# design.net
KiCad netlist of a schematic drawn in EAGLE
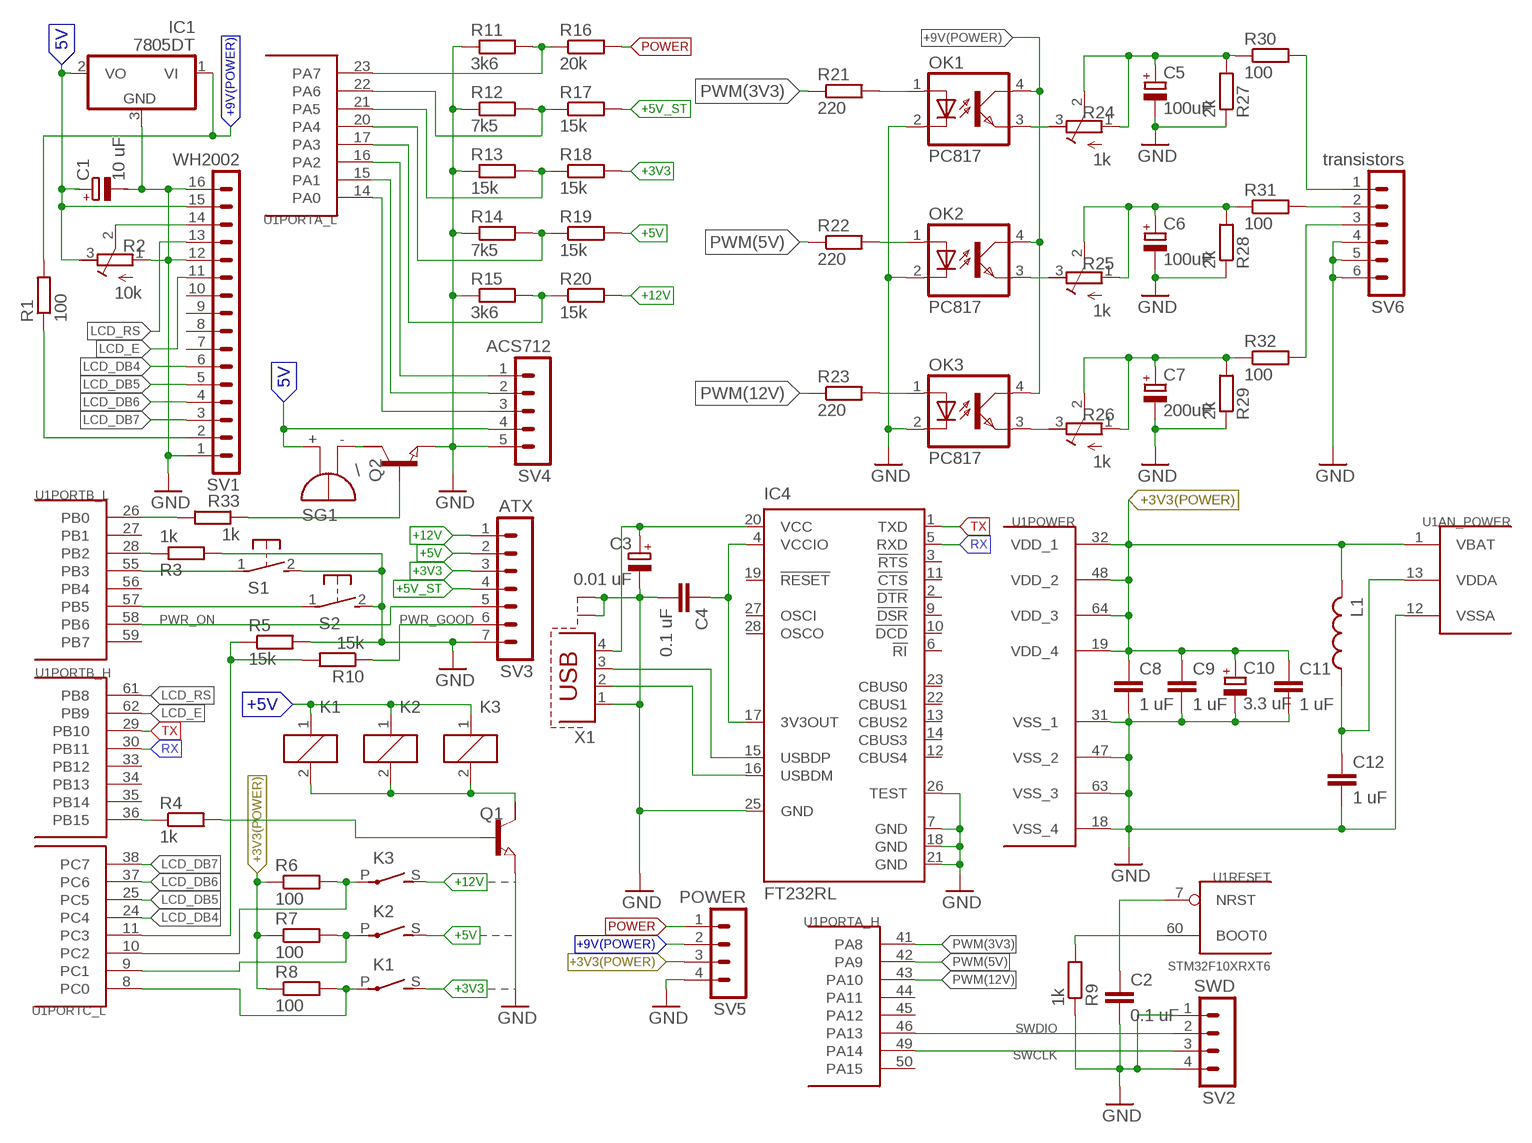
[diagram p0: schematic, sheet 1]

(export (version "E")
  (design (tool "Eeschema 10.0.6"))
  (components
    (comp (ref "C1")
      (value "10 uF")
      (footprint "eagle-import:140CLH-0810")
      (libsource (lib "eagle-import") (part "CPOL-EU140CLH-0810"))
    )
    (comp (ref "C2")
      (value "0.1 uF")
      (footprint "eagle-import:C1206")
      (libsource (lib "eagle-import") (part "C-EUC1206"))
    )
    (comp (ref "C3")
      (value "0.01 uF")
      (footprint "eagle-import:140CLH-0810")
      (libsource (lib "eagle-import") (part "CPOL-EU140CLH-0810"))
    )
    (comp (ref "C4")
      (value "0.1 uF")
      (footprint "eagle-import:C1206")
      (libsource (lib "eagle-import") (part "C-EUC1206"))
    )
    (comp (ref "C5")
      (value "100uF")
      (footprint "eagle-import:140CLH-0810")
      (libsource (lib "eagle-import") (part "CPOL-EU140CLH-0810"))
    )
    (comp (ref "C6")
      (value "100uF")
      (footprint "eagle-import:140CLH-0810")
      (libsource (lib "eagle-import") (part "CPOL-EU140CLH-0810"))
    )
    (comp (ref "C7")
      (value "200uF")
      (footprint "eagle-import:140CLH-0810")
      (libsource (lib "eagle-import") (part "CPOL-EU140CLH-0810"))
    )
    (comp (ref "C8")
      (value "1 uF")
      (footprint "eagle-import:C1206")
      (libsource (lib "eagle-import") (part "C-EUC1206"))
    )
    (comp (ref "C9")
      (value "1 uF")
      (footprint "eagle-import:C1206")
      (libsource (lib "eagle-import") (part "C-EUC1206"))
    )
    (comp (ref "C10")
      (value "3.3 uF")
      (footprint "eagle-import:140CLH-0810")
      (libsource (lib "eagle-import") (part "CPOL-EU140CLH-0810"))
    )
    (comp (ref "C11")
      (value "1 uF")
      (footprint "eagle-import:C1206")
      (libsource (lib "eagle-import") (part "C-EUC1206"))
    )
    (comp (ref "C12")
      (value "1 uF")
      (footprint "eagle-import:C1206")
      (libsource (lib "eagle-import") (part "C-EUC1206"))
    )
    (comp (ref "IC1")
      (value "7805DT")
      (footprint "eagle-import:TO252")
      (libsource (lib "eagle-import") (part "78DT05"))
    )
    (comp (ref "IC4")
      (value "FT232RL")
      (footprint "eagle-import:SSOP28")
      (libsource (lib "eagle-import") (part "FT232RL"))
    )
    (comp (ref "K1")
      (value "G2RA")
      (footprint "eagle-import:G2RA")
      (libsource (lib "eagle-import") (part "G2RA"))
    )
    (comp (ref "K2")
      (value "G2RA")
      (footprint "eagle-import:G2RA")
      (libsource (lib "eagle-import") (part "G2RA"))
    )
    (comp (ref "K3")
      (value "G2RA")
      (footprint "eagle-import:G2RA")
      (libsource (lib "eagle-import") (part "G2RA"))
    )
    (comp (ref "L1")
      (value "L-USL1812")
      (footprint "eagle-import:L1812")
      (libsource (lib "eagle-import") (part "L-USL1812"))
    )
    (comp (ref "OK1")
      (value "PC817")
      (footprint "eagle-import:DIL04")
      (fields (field (name "MPN") "PC817X4J000F"))
      (libsource (lib "eagle-import") (part "PC817"))
    )
    (comp (ref "OK2")
      (value "PC817")
      (footprint "eagle-import:DIL04")
      (fields (field (name "MPN") "PC817X4J000F"))
      (libsource (lib "eagle-import") (part "PC817"))
    )
    (comp (ref "OK3")
      (value "PC817")
      (footprint "eagle-import:DIL04")
      (fields (field (name "MPN") "PC817X4J000F"))
      (libsource (lib "eagle-import") (part "PC817"))
    )
    (comp (ref "Q1")
      (value "NPN-TRANSISTIOR-2COLSOT89")
      (footprint "eagle-import:SOT89")
      (libsource (lib "eagle-import") (part "NPN-TRANSISTIOR-2COLSOT89"))
    )
    (comp (ref "Q2")
      (value "NPN-TRANSISTIOR-2COLSOT89")
      (footprint "eagle-import:SOT89")
      (libsource (lib "eagle-import") (part "NPN-TRANSISTIOR-2COLSOT89"))
    )
    (comp (ref "R1")
      (value "100")
      (footprint "eagle-import:M1206")
      (libsource (lib "eagle-import") (part "R-EU_M1206"))
    )
    (comp (ref "R2")
      (value "10k")
      (footprint "eagle-import:RTRIM4G_J")
      (libsource (lib "eagle-import") (part "R-TRIMM4G/J"))
    )
    (comp (ref "R3")
      (value "1k")
      (footprint "eagle-import:M1206")
      (libsource (lib "eagle-import") (part "R-EU_M1206"))
    )
    (comp (ref "R4")
      (value "1k")
      (footprint "eagle-import:M1206")
      (libsource (lib "eagle-import") (part "R-EU_M1206"))
    )
    (comp (ref "R5")
      (value "15k")
      (footprint "eagle-import:M1206")
      (libsource (lib "eagle-import") (part "R-EU_M1206"))
    )
    (comp (ref "R6")
      (value "100")
      (footprint "eagle-import:M1206")
      (libsource (lib "eagle-import") (part "R-EU_M1206"))
    )
    (comp (ref "R7")
      (value "100")
      (footprint "eagle-import:M1206")
      (libsource (lib "eagle-import") (part "R-EU_M1206"))
    )
    (comp (ref "R8")
      (value "100")
      (footprint "eagle-import:M1206")
      (libsource (lib "eagle-import") (part "R-EU_M1206"))
    )
    (comp (ref "R9")
      (value "1k")
      (footprint "eagle-import:R1206")
      (libsource (lib "eagle-import") (part "R-EU_R1206"))
    )
    (comp (ref "R10")
      (value "15k")
      (footprint "eagle-import:M1206")
      (libsource (lib "eagle-import") (part "R-EU_M1206"))
    )
    (comp (ref "R11")
      (value "3k6")
      (footprint "eagle-import:M1206")
      (libsource (lib "eagle-import") (part "R-EU_M1206"))
    )
    (comp (ref "R12")
      (value "7k5")
      (footprint "eagle-import:M1206")
      (libsource (lib "eagle-import") (part "R-EU_M1206"))
    )
    (comp (ref "R13")
      (value "15k")
      (footprint "eagle-import:M1206")
      (libsource (lib "eagle-import") (part "R-EU_M1206"))
    )
    (comp (ref "R14")
      (value "7k5")
      (footprint "eagle-import:M1206")
      (libsource (lib "eagle-import") (part "R-EU_M1206"))
    )
    (comp (ref "R15")
      (value "3k6")
      (footprint "eagle-import:M1206")
      (libsource (lib "eagle-import") (part "R-EU_M1206"))
    )
    (comp (ref "R16")
      (value "20k")
      (footprint "eagle-import:M1206")
      (libsource (lib "eagle-import") (part "R-EU_M1206"))
    )
    (comp (ref "R17")
      (value "15k")
      (footprint "eagle-import:M1206")
      (libsource (lib "eagle-import") (part "R-EU_M1206"))
    )
    (comp (ref "R18")
      (value "15k")
      (footprint "eagle-import:M1206")
      (libsource (lib "eagle-import") (part "R-EU_M1206"))
    )
    (comp (ref "R19")
      (value "15k")
      (footprint "eagle-import:M1206")
      (libsource (lib "eagle-import") (part "R-EU_M1206"))
    )
    (comp (ref "R20")
      (value "15k")
      (footprint "eagle-import:M1206")
      (libsource (lib "eagle-import") (part "R-EU_M1206"))
    )
    (comp (ref "R21")
      (value "220")
      (footprint "eagle-import:M1206")
      (libsource (lib "eagle-import") (part "R-EU_M1206"))
    )
    (comp (ref "R22")
      (value "220")
      (footprint "eagle-import:M1206")
      (libsource (lib "eagle-import") (part "R-EU_M1206"))
    )
    (comp (ref "R23")
      (value "220")
      (footprint "eagle-import:M1206")
      (libsource (lib "eagle-import") (part "R-EU_M1206"))
    )
    (comp (ref "R24")
      (value "1k")
      (footprint "eagle-import:RTRIM4G_J")
      (libsource (lib "eagle-import") (part "R-TRIMM4G/J"))
    )
    (comp (ref "R25")
      (value "1k")
      (footprint "eagle-import:RTRIM4G_J")
      (libsource (lib "eagle-import") (part "R-TRIMM4G/J"))
    )
    (comp (ref "R26")
      (value "1k")
      (footprint "eagle-import:RTRIM4G_J")
      (libsource (lib "eagle-import") (part "R-TRIMM4G/J"))
    )
    (comp (ref "R27")
      (value "2k")
      (footprint "eagle-import:M1206")
      (libsource (lib "eagle-import") (part "R-EU_M1206"))
    )
    (comp (ref "R28")
      (value "2k")
      (footprint "eagle-import:M1206")
      (libsource (lib "eagle-import") (part "R-EU_M1206"))
    )
    (comp (ref "R29")
      (value "2k")
      (footprint "eagle-import:M1206")
      (libsource (lib "eagle-import") (part "R-EU_M1206"))
    )
    (comp (ref "R30")
      (value "100")
      (footprint "eagle-import:M1206")
      (libsource (lib "eagle-import") (part "R-EU_M1206"))
    )
    (comp (ref "R31")
      (value "100")
      (footprint "eagle-import:M1206")
      (libsource (lib "eagle-import") (part "R-EU_M1206"))
    )
    (comp (ref "R32")
      (value "100")
      (footprint "eagle-import:M1206")
      (libsource (lib "eagle-import") (part "R-EU_M1206"))
    )
    (comp (ref "R33")
      (value "1k")
      (footprint "eagle-import:M1206")
      (libsource (lib "eagle-import") (part "R-EU_M1206"))
    )
    (comp (ref "S1")
      (value "31-XX")
      (footprint "eagle-import:B3F-31XX")
      (fields (field (name "MPN") "B3F-3100"))
      (libsource (lib "eagle-import") (part "31-XX"))
    )
    (comp (ref "S2")
      (value "31-XX")
      (footprint "eagle-import:B3F-31XX")
      (fields (field (name "MPN") "B3F-3100"))
      (libsource (lib "eagle-import") (part "31-XX"))
    )
    (comp (ref "SG1")
      (value "\\")
      (footprint "eagle-import:F_BC35")
      (libsource (lib "eagle-import") (part "F/BC35"))
    )
    (comp (ref "SV1")
      (value "WH2002")
      (footprint "eagle-import:MICS-16")
      (libsource (lib "eagle-import") (part "MICS-16"))
    )
    (comp (ref "SV2")
      (value "SWD")
      (footprint "eagle-import:MA04-1")
      (libsource (lib "eagle-import") (part "MA04-1"))
    )
    (comp (ref "SV3")
      (value "ATX")
      (footprint "eagle-import:MA07-1")
      (libsource (lib "eagle-import") (part "MA07-1"))
    )
    (comp (ref "SV4")
      (value "ACS712")
      (footprint "eagle-import:MA05-1")
      (libsource (lib "eagle-import") (part "MA05-1"))
    )
    (comp (ref "SV5")
      (value "POWER")
      (footprint "eagle-import:MA04-1")
      (libsource (lib "eagle-import") (part "MA04-1"))
    )
    (comp (ref "SV6")
      (value "transistors")
      (footprint "eagle-import:MA06-1")
      (libsource (lib "eagle-import") (part "MA06-1"))
    )
    (comp (ref "U1")
      (value "STM32F10XRXT6")
      (footprint "eagle-import:TQFP64")
      (libsource (lib "eagle-import") (part "STM32F10XRXT6"))
    )
    (comp (ref "X1")
      (value "PN61729-S")
      (footprint "eagle-import:PN61729-S")
      (libsource (lib "eagle-import") (part "PN61729-S"))
    )
  )
  (nets
    (net (code "1") (name "+3V3") (class "Default")
      (node (ref "K1") (pin "S") (pinfunction "S_S") (pintype "passive"))
      (node (ref "R18") (pin "2") (pinfunction "2_2") (pintype "passive"))
      (node (ref "SV3") (pin "3") (pinfunction "3_3") (pintype "passive"))
    )
    (net (code "2") (name "+3V3(POWER)") (class "Default")
      (node (ref "C10") (pin "+") (pinfunction "+_+") (pintype "passive"))
      (node (ref "C11") (pin "1") (pinfunction "1_1") (pintype "passive"))
      (node (ref "C8") (pin "1") (pinfunction "1_1") (pintype "passive"))
      (node (ref "C9") (pin "1") (pinfunction "1_1") (pintype "passive"))
      (node (ref "L1") (pin "2") (pinfunction "2_2") (pintype "passive"))
      (node (ref "SV5") (pin "3") (pinfunction "3_3") (pintype "passive"))
      (node (ref "U1") (pin "1") (pinfunction "VBAT_1") (pintype "power_in"))
      (node (ref "U1") (pin "19") (pinfunction "VDD_4_19") (pintype "power_in"))
      (node (ref "U1") (pin "32") (pinfunction "VDD_1_32") (pintype "power_in"))
      (node (ref "U1") (pin "48") (pinfunction "VDD_2_48") (pintype "power_in"))
      (node (ref "U1") (pin "64") (pinfunction "VDD_3_64") (pintype "power_in"))
    )
    (net (code "3") (name "+5V") (class "Default")
      (node (ref "K1") (pin "1") (pinfunction "1_1") (pintype "passive"))
      (node (ref "K2") (pin "1") (pinfunction "1_1") (pintype "passive"))
      (node (ref "K2") (pin "S") (pinfunction "S_S") (pintype "passive"))
      (node (ref "K3") (pin "1") (pinfunction "1_1") (pintype "passive"))
      (node (ref "R19") (pin "2") (pinfunction "2_2") (pintype "passive"))
      (node (ref "SV3") (pin "2") (pinfunction "2_2") (pintype "passive"))
    )
    (net (code "4") (name "+5V_ST") (class "Default")
      (node (ref "R17") (pin "2") (pinfunction "2_2") (pintype "passive"))
      (node (ref "SV3") (pin "4") (pinfunction "4_4") (pintype "passive"))
    )
    (net (code "5") (name "+9V(POWER)") (class "Default")
      (node (ref "IC1") (pin "1") (pinfunction "VI_1") (pintype "input"))
      (node (ref "OK1") (pin "4") (pinfunction "COL_4") (pintype "passive"))
      (node (ref "OK2") (pin "4") (pinfunction "COL_4") (pintype "passive"))
      (node (ref "OK3") (pin "4") (pinfunction "COL_4") (pintype "passive"))
      (node (ref "R1") (pin "2") (pinfunction "2_2") (pintype "passive"))
      (node (ref "SV5") (pin "2") (pinfunction "2_2") (pintype "passive"))
    )
    (net (code "6") (name "+12V") (class "Default")
      (node (ref "K3") (pin "S") (pinfunction "S_S") (pintype "passive"))
      (node (ref "R20") (pin "2") (pinfunction "2_2") (pintype "passive"))
      (node (ref "SV3") (pin "1") (pinfunction "1_1") (pintype "passive"))
    )
    (net (code "7") (name "/PWR_GOOD") (class "Default")
      (node (ref "R10") (pin "1") (pinfunction "1_1") (pintype "passive"))
      (node (ref "SV3") (pin "6") (pinfunction "6_6") (pintype "passive"))
    )
    (net (code "8") (name "/PWR_ON") (class "Default")
      (node (ref "SV3") (pin "5") (pinfunction "5_5") (pintype "passive"))
      (node (ref "U1") (pin "58") (pinfunction "PB6_58") (pintype "bidirectional"))
    )
    (net (code "9") (name "/SWCLK") (class "Default")
      (node (ref "SV2") (pin "3") (pinfunction "3_3") (pintype "passive"))
      (node (ref "U1") (pin "49") (pinfunction "PA14_49") (pintype "bidirectional"))
    )
    (net (code "10") (name "/SWDIO") (class "Default")
      (node (ref "SV2") (pin "2") (pinfunction "2_2") (pintype "passive"))
      (node (ref "U1") (pin "46") (pinfunction "PA13_46") (pintype "bidirectional"))
    )
    (net (code "11") (name "5V") (class "Default")
      (node (ref "C1") (pin "+") (pinfunction "+_+") (pintype "passive"))
      (node (ref "IC1") (pin "2") (pinfunction "VO_2") (pintype "passive"))
      (node (ref "R2") (pin "3") (pinfunction "A_3") (pintype "passive"))
      (node (ref "SG1") (pin "+") (pinfunction "+_+") (pintype "passive"))
      (node (ref "SV1") (pin "15") (pinfunction "15_15") (pintype "passive"))
      (node (ref "SV4") (pin "4") (pinfunction "4_4") (pintype "passive"))
    )
    (net (code "12") (name "GND") (class "Default")
      (node (ref "C1") (pin "-") (pinfunction "-_-") (pintype "passive"))
      (node (ref "C10") (pin "-") (pinfunction "-_-") (pintype "passive"))
      (node (ref "C11") (pin "2") (pinfunction "2_2") (pintype "passive"))
      (node (ref "C12") (pin "2") (pinfunction "2_2") (pintype "passive"))
      (node (ref "C2") (pin "2") (pinfunction "2_2") (pintype "passive"))
      (node (ref "C3") (pin "-") (pinfunction "-_-") (pintype "passive"))
      (node (ref "C4") (pin "2") (pinfunction "2_2") (pintype "passive"))
      (node (ref "C5") (pin "-") (pinfunction "-_-") (pintype "passive"))
      (node (ref "C6") (pin "-") (pinfunction "-_-") (pintype "passive"))
      (node (ref "C7") (pin "-") (pinfunction "-_-") (pintype "passive"))
      (node (ref "C8") (pin "2") (pinfunction "2_2") (pintype "passive"))
      (node (ref "C9") (pin "2") (pinfunction "2_2") (pintype "passive"))
      (node (ref "IC1") (pin "3") (pinfunction "GND_3") (pintype "passive"))
      (node (ref "IC4") (pin "18") (pinfunction "GND_18") (pintype "power_in"))
      (node (ref "IC4") (pin "21") (pinfunction "GND_21") (pintype "power_in"))
      (node (ref "IC4") (pin "25") (pinfunction "GND_25") (pintype "power_in"))
      (node (ref "IC4") (pin "26") (pinfunction "TEST_26") (pintype "input"))
      (node (ref "IC4") (pin "7") (pinfunction "GND_7") (pintype "power_in"))
      (node (ref "OK1") (pin "2") (pinfunction "C_2") (pintype "passive"))
      (node (ref "OK2") (pin "2") (pinfunction "C_2") (pintype "passive"))
      (node (ref "OK3") (pin "2") (pinfunction "C_2") (pintype "passive"))
      (node (ref "Q1") (pin "3") (pinfunction "E_3") (pintype "passive"))
      (node (ref "Q2") (pin "3") (pinfunction "E_3") (pintype "passive"))
      (node (ref "R11") (pin "1") (pinfunction "1_1") (pintype "passive"))
      (node (ref "R12") (pin "1") (pinfunction "1_1") (pintype "passive"))
      (node (ref "R13") (pin "1") (pinfunction "1_1") (pintype "passive"))
      (node (ref "R14") (pin "1") (pinfunction "1_1") (pintype "passive"))
      (node (ref "R15") (pin "1") (pinfunction "1_1") (pintype "passive"))
      (node (ref "R2") (pin "1") (pinfunction "E_1") (pintype "passive"))
      (node (ref "R27") (pin "1") (pinfunction "1_1") (pintype "passive"))
      (node (ref "R28") (pin "1") (pinfunction "1_1") (pintype "passive"))
      (node (ref "R29") (pin "1") (pinfunction "1_1") (pintype "passive"))
      (node (ref "R3") (pin "2") (pinfunction "2_2") (pintype "passive"))
      (node (ref "R5") (pin "2") (pinfunction "2_2") (pintype "passive"))
      (node (ref "R9") (pin "1") (pinfunction "1_1") (pintype "passive"))
      (node (ref "S1") (pin "2") (pinfunction "S_2") (pintype "passive"))
      (node (ref "S2") (pin "2") (pinfunction "S_2") (pintype "passive"))
      (node (ref "SV1") (pin "1") (pinfunction "1_1") (pintype "passive"))
      (node (ref "SV1") (pin "12") (pinfunction "12_12") (pintype "passive"))
      (node (ref "SV1") (pin "16") (pinfunction "16_16") (pintype "passive"))
      (node (ref "SV2") (pin "1") (pinfunction "1_1") (pintype "passive"))
      (node (ref "SV2") (pin "4") (pinfunction "4_4") (pintype "passive"))
      (node (ref "SV3") (pin "7") (pinfunction "7_7") (pintype "passive"))
      (node (ref "SV4") (pin "5") (pinfunction "5_5") (pintype "passive"))
      (node (ref "SV5") (pin "4") (pinfunction "4_4") (pintype "passive"))
      (node (ref "SV6") (pin "4") (pinfunction "4_4") (pintype "passive"))
      (node (ref "SV6") (pin "5") (pinfunction "5_5") (pintype "passive"))
      (node (ref "SV6") (pin "6") (pinfunction "6_6") (pintype "passive"))
      (node (ref "U1") (pin "12") (pinfunction "VSSA_12") (pintype "power_in"))
      (node (ref "U1") (pin "18") (pinfunction "VSS_4_18") (pintype "power_in"))
      (node (ref "U1") (pin "31") (pinfunction "VSS_1_31") (pintype "power_in"))
      (node (ref "U1") (pin "47") (pinfunction "VSS_2_47") (pintype "power_in"))
      (node (ref "U1") (pin "63") (pinfunction "VSS_3_63") (pintype "power_in"))
      (node (ref "X1") (pin "1") (pinfunction "1_1") (pintype "passive"))
      (node (ref "X1") (pin "S1") (pinfunction "S1_S1") (pintype "passive"))
      (node (ref "X1") (pin "S2") (pinfunction "S2_S2") (pintype "passive"))
    )
    (net (code "13") (name "LCD_DB4") (class "Default")
      (node (ref "SV1") (pin "6") (pinfunction "6_6") (pintype "passive"))
      (node (ref "U1") (pin "24") (pinfunction "PC4_24") (pintype "bidirectional"))
    )
    (net (code "14") (name "LCD_DB5") (class "Default")
      (node (ref "SV1") (pin "5") (pinfunction "5_5") (pintype "passive"))
      (node (ref "U1") (pin "25") (pinfunction "PC5_25") (pintype "bidirectional"))
    )
    (net (code "15") (name "LCD_DB6") (class "Default")
      (node (ref "SV1") (pin "4") (pinfunction "4_4") (pintype "passive"))
      (node (ref "U1") (pin "37") (pinfunction "PC6_37") (pintype "bidirectional"))
    )
    (net (code "16") (name "LCD_DB7") (class "Default")
      (node (ref "SV1") (pin "3") (pinfunction "3_3") (pintype "passive"))
      (node (ref "U1") (pin "38") (pinfunction "PC7_38") (pintype "bidirectional"))
    )
    (net (code "17") (name "LCD_E") (class "Default")
      (node (ref "SV1") (pin "11") (pinfunction "11_11") (pintype "passive"))
      (node (ref "U1") (pin "62") (pinfunction "PB9_62") (pintype "bidirectional"))
    )
    (net (code "18") (name "LCD_RS") (class "Default")
      (node (ref "SV1") (pin "13") (pinfunction "13_13") (pintype "passive"))
      (node (ref "U1") (pin "61") (pinfunction "PB8_61") (pintype "bidirectional"))
    )
    (net (code "19") (name "Net-(IC4-3V3OUT)") (class "Default")
      (node (ref "C4") (pin "1") (pinfunction "1_1") (pintype "passive"))
      (node (ref "IC4") (pin "17") (pinfunction "3V3OUT_17") (pintype "output"))
      (node (ref "IC4") (pin "4") (pinfunction "VCCIO_4") (pintype "power_in"))
    )
    (net (code "20") (name "Net-(IC4-USBDM)") (class "Default")
      (node (ref "IC4") (pin "16") (pinfunction "USBDM_16") (pintype "bidirectional"))
      (node (ref "X1") (pin "2") (pinfunction "2_2") (pintype "passive"))
    )
    (net (code "21") (name "Net-(IC4-USBDP)") (class "Default")
      (node (ref "IC4") (pin "15") (pinfunction "USBDP_15") (pintype "bidirectional"))
      (node (ref "X1") (pin "3") (pinfunction "3_3") (pintype "passive"))
    )
    (net (code "22") (name "Net-(IC4-VCC)") (class "Default")
      (node (ref "C3") (pin "+") (pinfunction "+_+") (pintype "passive"))
      (node (ref "IC4") (pin "20") (pinfunction "VCC_20") (pintype "power_in"))
      (node (ref "X1") (pin "4") (pinfunction "4_4") (pintype "passive"))
    )
    (net (code "23") (name "Net-(OK1-A)") (class "Default")
      (node (ref "OK1") (pin "1") (pinfunction "A_1") (pintype "passive"))
      (node (ref "R21") (pin "2") (pinfunction "2_2") (pintype "passive"))
    )
    (net (code "24") (name "Net-(OK1-EMIT)") (class "Default")
      (node (ref "OK1") (pin "3") (pinfunction "EMIT_3") (pintype "passive"))
      (node (ref "R24") (pin "3") (pinfunction "A_3") (pintype "passive"))
    )
    (net (code "25") (name "Net-(OK2-A)") (class "Default")
      (node (ref "OK2") (pin "1") (pinfunction "A_1") (pintype "passive"))
      (node (ref "R22") (pin "2") (pinfunction "2_2") (pintype "passive"))
    )
    (net (code "26") (name "Net-(OK2-EMIT)") (class "Default")
      (node (ref "OK2") (pin "3") (pinfunction "EMIT_3") (pintype "passive"))
      (node (ref "R25") (pin "3") (pinfunction "A_3") (pintype "passive"))
    )
    (net (code "27") (name "Net-(OK3-A)") (class "Default")
      (node (ref "OK3") (pin "1") (pinfunction "A_1") (pintype "passive"))
      (node (ref "R23") (pin "2") (pinfunction "2_2") (pintype "passive"))
    )
    (net (code "28") (name "Net-(OK3-EMIT)") (class "Default")
      (node (ref "OK3") (pin "3") (pinfunction "EMIT_3") (pintype "passive"))
      (node (ref "R26") (pin "3") (pinfunction "A_3") (pintype "passive"))
    )
    (net (code "29") (name "Net-(Q1-B)") (class "Default")
      (node (ref "Q1") (pin "1") (pinfunction "B_1") (pintype "passive"))
      (node (ref "R4") (pin "2") (pinfunction "2_2") (pintype "passive"))
    )
    (net (code "30") (name "Net-(Q1-C)") (class "Default")
      (node (ref "K1") (pin "2") (pinfunction "2_2") (pintype "passive"))
      (node (ref "K2") (pin "2") (pinfunction "2_2") (pintype "passive"))
      (node (ref "K3") (pin "2") (pinfunction "2_2") (pintype "passive"))
      (node (ref "Q1") (pin "2") (pinfunction "C_2") (pintype "passive"))
    )
    (net (code "31") (name "Net-(Q2-B)") (class "Default")
      (node (ref "Q2") (pin "1") (pinfunction "B_1") (pintype "passive"))
      (node (ref "R33") (pin "1") (pinfunction "1_1") (pintype "passive"))
    )
    (net (code "32") (name "Net-(Q2-C)") (class "Default")
      (node (ref "Q2") (pin "2") (pinfunction "C_2") (pintype "passive"))
      (node (ref "SG1") (pin "-") (pinfunction "-_-") (pintype "passive"))
    )
    (net (code "33") (name "Net-(R1-Pad1)") (class "Default")
      (node (ref "R1") (pin "1") (pinfunction "1_1") (pintype "passive"))
      (node (ref "SV1") (pin "2") (pinfunction "2_2") (pintype "passive"))
    )
    (net (code "34") (name "Net-(R2-S)") (class "Default")
      (node (ref "R2") (pin "2") (pinfunction "S_2") (pintype "passive"))
      (node (ref "SV1") (pin "14") (pinfunction "14_14") (pintype "passive"))
    )
    (net (code "35") (name "Net-(R6-Pad1)") (class "Default")
      (node (ref "R6") (pin "1") (pinfunction "1_1") (pintype "passive"))
      (node (ref "R7") (pin "1") (pinfunction "1_1") (pintype "passive"))
      (node (ref "R8") (pin "1") (pinfunction "1_1") (pintype "passive"))
    )
    (net (code "36") (name "Net-(R24-E)") (class "Default")
      (node (ref "C5") (pin "+") (pinfunction "+_+") (pintype "passive"))
      (node (ref "R24") (pin "1") (pinfunction "E_1") (pintype "passive"))
      (node (ref "R24") (pin "2") (pinfunction "S_2") (pintype "passive"))
      (node (ref "R27") (pin "2") (pinfunction "2_2") (pintype "passive"))
      (node (ref "R30") (pin "1") (pinfunction "1_1") (pintype "passive"))
    )
    (net (code "37") (name "Net-(R25-E)") (class "Default")
      (node (ref "C6") (pin "+") (pinfunction "+_+") (pintype "passive"))
      (node (ref "R25") (pin "1") (pinfunction "E_1") (pintype "passive"))
      (node (ref "R25") (pin "2") (pinfunction "S_2") (pintype "passive"))
      (node (ref "R28") (pin "2") (pinfunction "2_2") (pintype "passive"))
      (node (ref "R31") (pin "1") (pinfunction "1_1") (pintype "passive"))
    )
    (net (code "38") (name "Net-(R26-E)") (class "Default")
      (node (ref "C7") (pin "+") (pinfunction "+_+") (pintype "passive"))
      (node (ref "R26") (pin "1") (pinfunction "E_1") (pintype "passive"))
      (node (ref "R26") (pin "2") (pinfunction "S_2") (pintype "passive"))
      (node (ref "R29") (pin "2") (pinfunction "2_2") (pintype "passive"))
      (node (ref "R32") (pin "1") (pinfunction "1_1") (pintype "passive"))
    )
    (net (code "39") (name "Net-(R30-Pad2)") (class "Default")
      (node (ref "R30") (pin "2") (pinfunction "2_2") (pintype "passive"))
      (node (ref "SV6") (pin "1") (pinfunction "1_1") (pintype "passive"))
    )
    (net (code "40") (name "Net-(R31-Pad2)") (class "Default")
      (node (ref "R31") (pin "2") (pinfunction "2_2") (pintype "passive"))
      (node (ref "SV6") (pin "2") (pinfunction "2_2") (pintype "passive"))
    )
    (net (code "41") (name "Net-(R32-Pad2)") (class "Default")
      (node (ref "R32") (pin "2") (pinfunction "2_2") (pintype "passive"))
      (node (ref "SV6") (pin "3") (pinfunction "3_3") (pintype "passive"))
    )
    (net (code "42") (name "Net-(S1-P)") (class "Default")
      (node (ref "S1") (pin "1") (pinfunction "P_1") (pintype "passive"))
      (node (ref "U1") (pin "55") (pinfunction "PB3_55") (pintype "bidirectional"))
    )
    (net (code "43") (name "Net-(S2-P)") (class "Default")
      (node (ref "S2") (pin "1") (pinfunction "P_1") (pintype "passive"))
      (node (ref "U1") (pin "57") (pinfunction "PB5_57") (pintype "bidirectional"))
    )
    (net (code "44") (name "Net-(U1A-VDDA)") (class "Default")
      (node (ref "C12") (pin "1") (pinfunction "1_1") (pintype "passive"))
      (node (ref "L1") (pin "1") (pinfunction "1_1") (pintype "passive"))
      (node (ref "U1") (pin "13") (pinfunction "VDDA_13") (pintype "power_in"))
    )
    (net (code "45") (name "Net-(U1C-PA0)") (class "Default")
      (node (ref "SV4") (pin "3") (pinfunction "3_3") (pintype "passive"))
      (node (ref "U1") (pin "14") (pinfunction "PA0_14") (pintype "bidirectional"))
    )
    (net (code "46") (name "Net-(U1C-PA1)") (class "Default")
      (node (ref "SV4") (pin "2") (pinfunction "2_2") (pintype "passive"))
      (node (ref "U1") (pin "15") (pinfunction "PA1_15") (pintype "bidirectional"))
    )
    (net (code "47") (name "Net-(U1C-PA2)") (class "Default")
      (node (ref "SV4") (pin "1") (pinfunction "1_1") (pintype "passive"))
      (node (ref "U1") (pin "16") (pinfunction "PA2_16") (pintype "bidirectional"))
    )
    (net (code "48") (name "Net-(U1C-PA3)") (class "Default")
      (node (ref "R15") (pin "2") (pinfunction "2_2") (pintype "passive"))
      (node (ref "R20") (pin "1") (pinfunction "1_1") (pintype "passive"))
      (node (ref "U1") (pin "17") (pinfunction "PA3_17") (pintype "bidirectional"))
    )
    (net (code "49") (name "Net-(U1C-PA4)") (class "Default")
      (node (ref "R14") (pin "2") (pinfunction "2_2") (pintype "passive"))
      (node (ref "R19") (pin "1") (pinfunction "1_1") (pintype "passive"))
      (node (ref "U1") (pin "20") (pinfunction "PA4_20") (pintype "bidirectional"))
    )
    (net (code "50") (name "Net-(U1C-PA5)") (class "Default")
      (node (ref "R13") (pin "2") (pinfunction "2_2") (pintype "passive"))
      (node (ref "R18") (pin "1") (pinfunction "1_1") (pintype "passive"))
      (node (ref "U1") (pin "21") (pinfunction "PA5_21") (pintype "bidirectional"))
    )
    (net (code "51") (name "Net-(U1C-PA6)") (class "Default")
      (node (ref "R12") (pin "2") (pinfunction "2_2") (pintype "passive"))
      (node (ref "R17") (pin "1") (pinfunction "1_1") (pintype "passive"))
      (node (ref "U1") (pin "22") (pinfunction "PA6_22") (pintype "bidirectional"))
    )
    (net (code "52") (name "Net-(U1C-PA7)") (class "Default")
      (node (ref "R11") (pin "2") (pinfunction "2_2") (pintype "passive"))
      (node (ref "R16") (pin "1") (pinfunction "1_1") (pintype "passive"))
      (node (ref "U1") (pin "23") (pinfunction "PA7_23") (pintype "bidirectional"))
    )
    (net (code "53") (name "Net-(U1D-PB15)") (class "Default")
      (node (ref "R4") (pin "1") (pinfunction "1_1") (pintype "passive"))
      (node (ref "U1") (pin "36") (pinfunction "PB15_36") (pintype "bidirectional"))
    )
    (net (code "54") (name "Net-(U1E-PB0)") (class "Default")
      (node (ref "R33") (pin "2") (pinfunction "2_2") (pintype "passive"))
      (node (ref "U1") (pin "26") (pinfunction "PB0_26") (pintype "bidirectional"))
    )
    (net (code "55") (name "Net-(U1E-PB2)") (class "Default")
      (node (ref "R3") (pin "1") (pinfunction "1_1") (pintype "passive"))
      (node (ref "U1") (pin "28") (pinfunction "PB2_28") (pintype "bidirectional"))
    )
    (net (code "56") (name "Net-(U1G-PC0)") (class "Default")
      (node (ref "K1") (pin "P") (pinfunction "P_P") (pintype "passive"))
      (node (ref "R8") (pin "2") (pinfunction "2_2") (pintype "passive"))
      (node (ref "U1") (pin "8") (pinfunction "PC0_8") (pintype "bidirectional"))
    )
    (net (code "57") (name "Net-(U1G-PC1)") (class "Default")
      (node (ref "K2") (pin "P") (pinfunction "P_P") (pintype "passive"))
      (node (ref "R7") (pin "2") (pinfunction "2_2") (pintype "passive"))
      (node (ref "U1") (pin "9") (pinfunction "PC1_9") (pintype "bidirectional"))
    )
    (net (code "58") (name "Net-(U1G-PC2)") (class "Default")
      (node (ref "K3") (pin "P") (pinfunction "P_P") (pintype "passive"))
      (node (ref "R6") (pin "2") (pinfunction "2_2") (pintype "passive"))
      (node (ref "U1") (pin "10") (pinfunction "PC2_10") (pintype "bidirectional"))
    )
    (net (code "59") (name "Net-(U1G-PC3)") (class "Default")
      (node (ref "R10") (pin "2") (pinfunction "2_2") (pintype "passive"))
      (node (ref "R5") (pin "1") (pinfunction "1_1") (pintype "passive"))
      (node (ref "U1") (pin "11") (pinfunction "PC3_11") (pintype "bidirectional"))
    )
    (net (code "60") (name "Net-(U1J-BOOT0)") (class "Default")
      (node (ref "R9") (pin "2") (pinfunction "2_2") (pintype "passive"))
      (node (ref "U1") (pin "60") (pinfunction "BOOT0_60") (pintype "input"))
    )
    (net (code "61") (name "Net-(U1J-NRST)") (class "Default")
      (node (ref "C2") (pin "1") (pinfunction "1_1") (pintype "passive"))
      (node (ref "U1") (pin "7") (pinfunction "NRST_7") (pintype "input"))
    )
    (net (code "62") (name "POWER") (class "Default")
      (node (ref "R16") (pin "2") (pinfunction "2_2") (pintype "passive"))
      (node (ref "SV5") (pin "1") (pinfunction "1_1") (pintype "passive"))
    )
    (net (code "63") (name "PWM(3V3)") (class "Default")
      (node (ref "R21") (pin "1") (pinfunction "1_1") (pintype "passive"))
      (node (ref "U1") (pin "41") (pinfunction "PA8_41") (pintype "bidirectional"))
    )
    (net (code "64") (name "PWM(5V)") (class "Default")
      (node (ref "R22") (pin "1") (pinfunction "1_1") (pintype "passive"))
      (node (ref "U1") (pin "42") (pinfunction "PA9_42") (pintype "bidirectional"))
    )
    (net (code "65") (name "PWM(12V)") (class "Default")
      (node (ref "R23") (pin "1") (pinfunction "1_1") (pintype "passive"))
      (node (ref "U1") (pin "43") (pinfunction "PA10_43") (pintype "bidirectional"))
    )
    (net (code "66") (name "RX") (class "Default")
      (node (ref "IC4") (pin "5") (pinfunction "RXD_5") (pintype "input"))
      (node (ref "U1") (pin "30") (pinfunction "PB11_30") (pintype "bidirectional"))
    )
    (net (code "67") (name "TX") (class "Default")
      (node (ref "IC4") (pin "1") (pinfunction "TXD_1") (pintype "output"))
      (node (ref "U1") (pin "29") (pinfunction "PB10_29") (pintype "bidirectional"))
    )
    (net (code "68") (name "unconnected-(IC4-CBUS0-Pad23)") (class "Default")
      (node (ref "IC4") (pin "23") (pinfunction "CBUS0_23") (pintype "bidirectional"))
    )
    (net (code "69") (name "unconnected-(IC4-CBUS1-Pad22)") (class "Default")
      (node (ref "IC4") (pin "22") (pinfunction "CBUS1_22") (pintype "bidirectional"))
    )
    (net (code "70") (name "unconnected-(IC4-CBUS2-Pad13)") (class "Default")
      (node (ref "IC4") (pin "13") (pinfunction "CBUS2_13") (pintype "bidirectional"))
    )
    (net (code "71") (name "unconnected-(IC4-CBUS3-Pad14)") (class "Default")
      (node (ref "IC4") (pin "14") (pinfunction "CBUS3_14") (pintype "bidirectional"))
    )
    (net (code "72") (name "unconnected-(IC4-CBUS4-Pad12)") (class "Default")
      (node (ref "IC4") (pin "12") (pinfunction "CBUS4_12") (pintype "bidirectional"))
    )
    (net (code "73") (name "unconnected-(IC4-OSCI-Pad27)") (class "Default")
      (node (ref "IC4") (pin "27") (pinfunction "OSCI_27") (pintype "input"))
    )
    (net (code "74") (name "unconnected-(IC4-OSCO-Pad28)") (class "Default")
      (node (ref "IC4") (pin "28") (pinfunction "OSCO_28") (pintype "output"))
    )
    (net (code "75") (name "unconnected-(IC4-~{CTS}-Pad11)") (class "Default")
      (node (ref "IC4") (pin "11") (pinfunction "~{CTS}_11") (pintype "input"))
    )
    (net (code "76") (name "unconnected-(IC4-~{DCD}-Pad10)") (class "Default")
      (node (ref "IC4") (pin "10") (pinfunction "~{DCD}_10") (pintype "input"))
    )
    (net (code "77") (name "unconnected-(IC4-~{DSR}-Pad9)") (class "Default")
      (node (ref "IC4") (pin "9") (pinfunction "~{DSR}_9") (pintype "input"))
    )
    (net (code "78") (name "unconnected-(IC4-~{DTR}-Pad2)") (class "Default")
      (node (ref "IC4") (pin "2") (pinfunction "~{DTR}_2") (pintype "output"))
    )
    (net (code "79") (name "unconnected-(IC4-~{RESET}-Pad19)") (class "Default")
      (node (ref "IC4") (pin "19") (pinfunction "~{RESET}_19") (pintype "input"))
    )
    (net (code "80") (name "unconnected-(IC4-~{RI}-Pad6)") (class "Default")
      (node (ref "IC4") (pin "6") (pinfunction "~{RI}_6") (pintype "input"))
    )
    (net (code "81") (name "unconnected-(IC4-~{RTS}-Pad3)") (class "Default")
      (node (ref "IC4") (pin "3") (pinfunction "~{RTS}_3") (pintype "output"))
    )
    (net (code "82") (name "unconnected-(Q1-C{slash}-Pad2@1)") (class "Default")
      (node (ref "Q1") (pin "2@1") (pinfunction "C/_2@1") (pintype "passive"))
    )
    (net (code "83") (name "unconnected-(Q2-C{slash}-Pad2@1)") (class "Default")
      (node (ref "Q2") (pin "2@1") (pinfunction "C/_2@1") (pintype "passive"))
    )
    (net (code "84") (name "unconnected-(SV1-Pad7)") (class "Default")
      (node (ref "SV1") (pin "7") (pinfunction "7_7") (pintype "passive"))
    )
    (net (code "85") (name "unconnected-(SV1-Pad8)") (class "Default")
      (node (ref "SV1") (pin "8") (pinfunction "8_8") (pintype "passive"))
    )
    (net (code "86") (name "unconnected-(SV1-Pad9)") (class "Default")
      (node (ref "SV1") (pin "9") (pinfunction "9_9") (pintype "passive"))
    )
    (net (code "87") (name "unconnected-(SV1-Pad10)") (class "Default")
      (node (ref "SV1") (pin "10") (pinfunction "10_10") (pintype "passive"))
    )
    (net (code "88") (name "unconnected-(U1B-PA11-Pad44)") (class "Default")
      (node (ref "U1") (pin "44") (pinfunction "PA11_44") (pintype "bidirectional"))
    )
    (net (code "89") (name "unconnected-(U1B-PA12-Pad45)") (class "Default")
      (node (ref "U1") (pin "45") (pinfunction "PA12_45") (pintype "bidirectional"))
    )
    (net (code "90") (name "unconnected-(U1B-PA15-Pad50)") (class "Default")
      (node (ref "U1") (pin "50") (pinfunction "PA15_50") (pintype "bidirectional"))
    )
    (net (code "91") (name "unconnected-(U1D-PB12-Pad33)") (class "Default")
      (node (ref "U1") (pin "33") (pinfunction "PB12_33") (pintype "bidirectional"))
    )
    (net (code "92") (name "unconnected-(U1D-PB13-Pad34)") (class "Default")
      (node (ref "U1") (pin "34") (pinfunction "PB13_34") (pintype "bidirectional"))
    )
    (net (code "93") (name "unconnected-(U1D-PB14-Pad35)") (class "Default")
      (node (ref "U1") (pin "35") (pinfunction "PB14_35") (pintype "bidirectional"))
    )
    (net (code "94") (name "unconnected-(U1E-PB1-Pad27)") (class "Default")
      (node (ref "U1") (pin "27") (pinfunction "PB1_27") (pintype "bidirectional"))
    )
    (net (code "95") (name "unconnected-(U1E-PB4-Pad56)") (class "Default")
      (node (ref "U1") (pin "56") (pinfunction "PB4_56") (pintype "bidirectional"))
    )
    (net (code "96") (name "unconnected-(U1E-PB7-Pad59)") (class "Default")
      (node (ref "U1") (pin "59") (pinfunction "PB7_59") (pintype "bidirectional"))
    )
  )
)
